# Julia_ABL_Board_V2.net
KiCad netlist of a schematic drawn in EAGLE
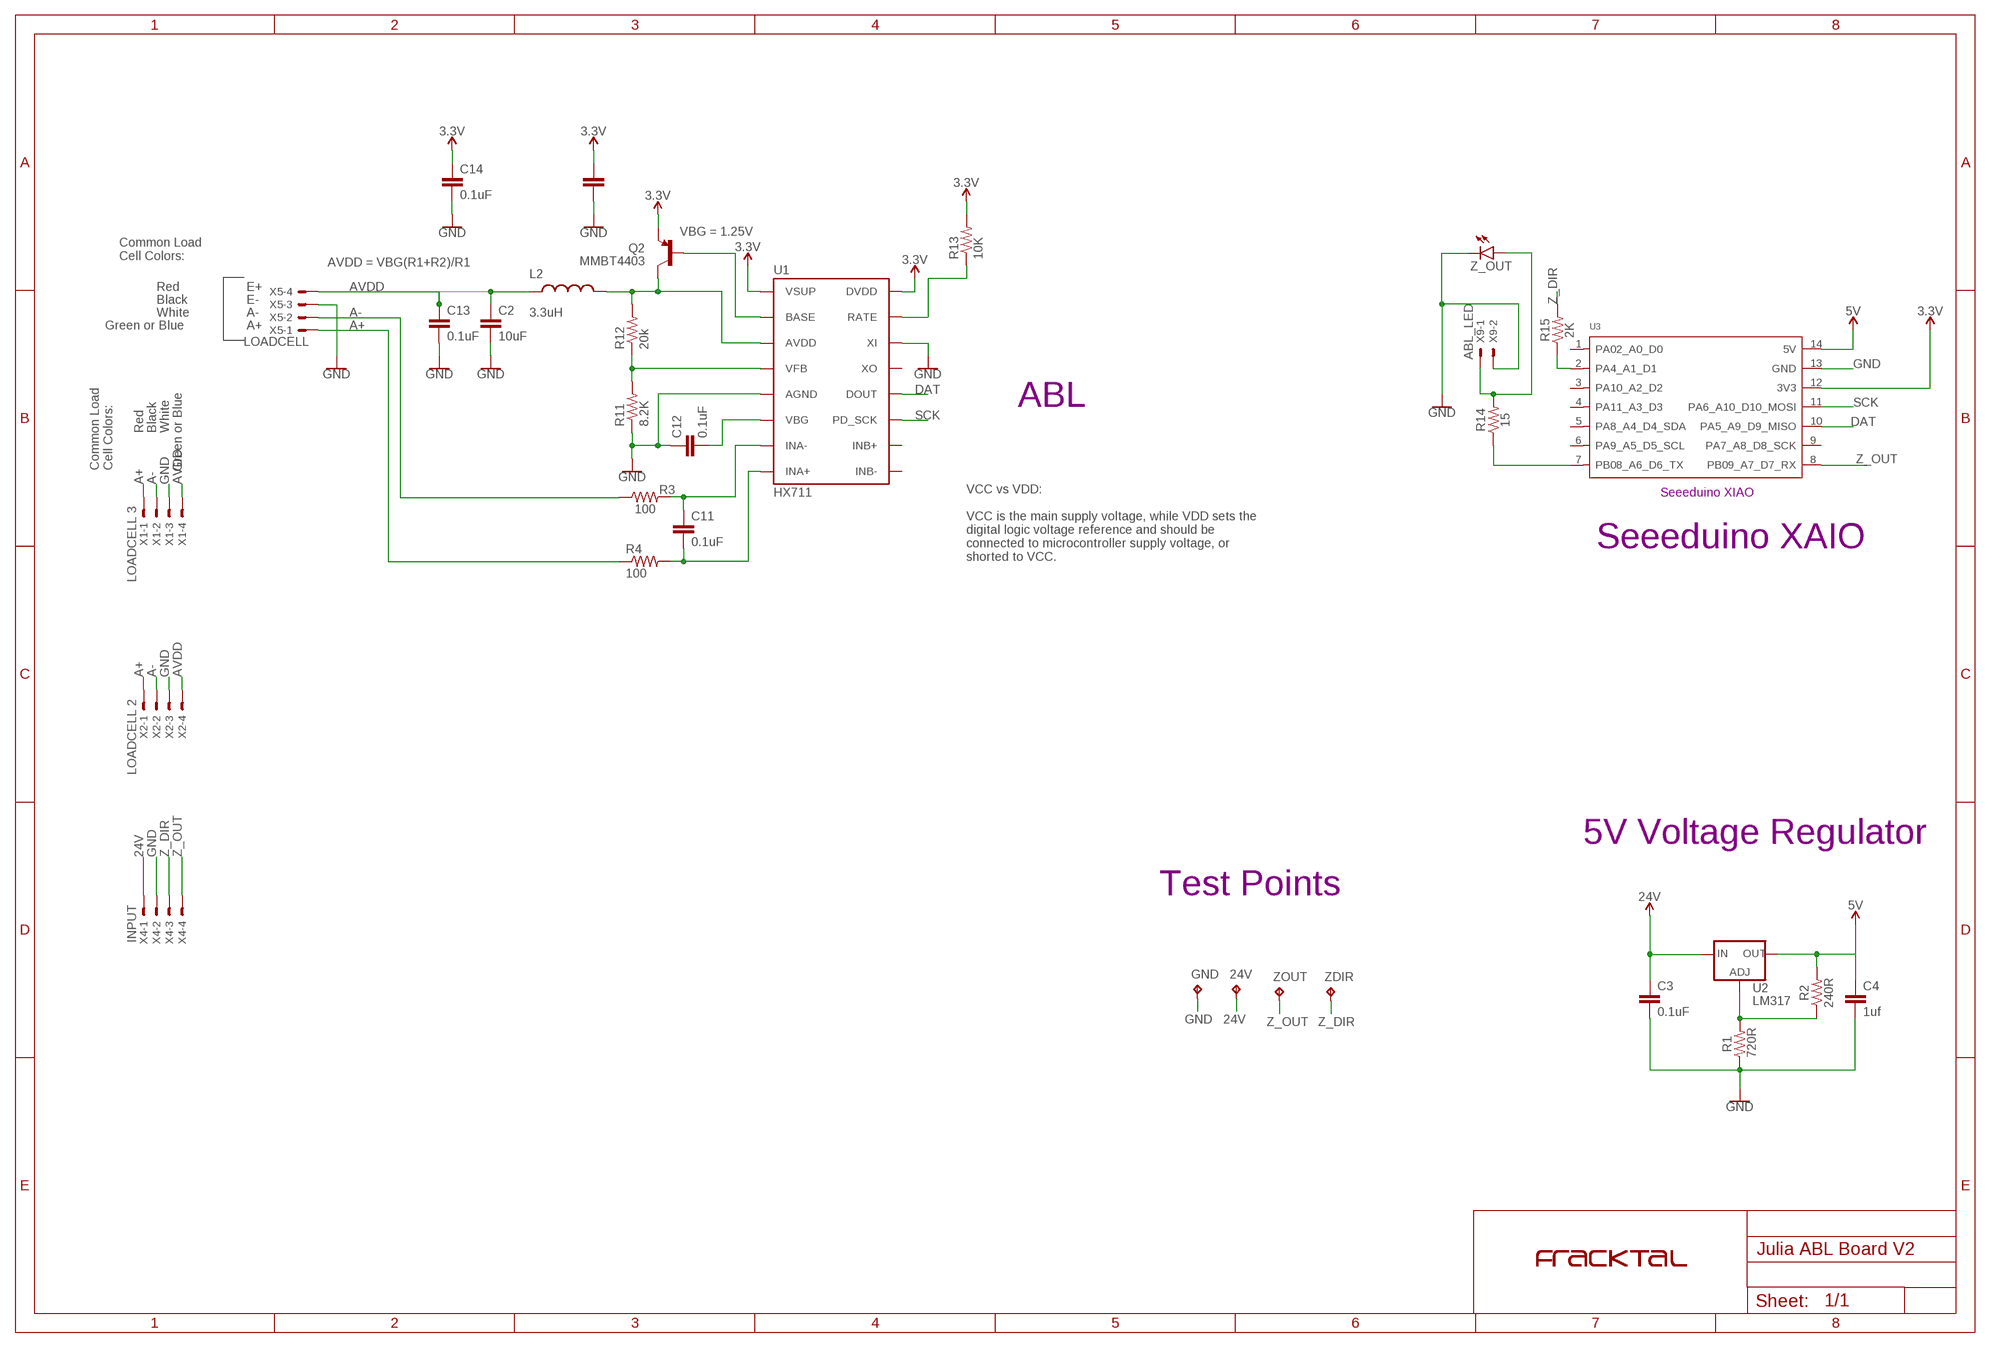
[diagram p0: schematic, sheet 1]

(export (version "E")
  (design (tool "Eeschema 10.0.6"))
  (components
    (comp (ref "24V")
      (value "TPB2,54")
      (footprint "eagle-import:B2,54")
      (libsource (lib "eagle-import") (part "TPB2,54"))
    )
    (comp (ref "C1")
      (value "10uF")
      (footprint "eagle-import:1210")
      (libsource (lib "eagle-import") (part "10UF50V20%(1210)"))
    )
    (comp (ref "C2")
      (value "10uF")
      (footprint "eagle-import:1210")
      (libsource (lib "eagle-import") (part "10UF50V20%(1210)"))
    )
    (comp (ref "C3")
      (value "0.1uF")
      (footprint "eagle-import:0603")
      (libsource (lib "eagle-import") (part "9.0PF-0603-50V-10%"))
    )
    (comp (ref "C4")
      (value "1uf")
      (footprint "eagle-import:0603")
      (libsource (lib "eagle-import") (part "9.0PF-0603-50V-10%"))
    )
    (comp (ref "C11")
      (value "0.1uF")
      (footprint "eagle-import:0603-CAP")
      (libsource (lib "eagle-import") (part "0.1UF-25V-5%(0603)"))
    )
    (comp (ref "C12")
      (value "0.1uF")
      (footprint "eagle-import:0603-CAP")
      (libsource (lib "eagle-import") (part "0.1UF-25V-5%(0603)"))
    )
    (comp (ref "C13")
      (value "0.1uF")
      (footprint "eagle-import:0603-CAP")
      (libsource (lib "eagle-import") (part "0.1UF-25V-5%(0603)"))
    )
    (comp (ref "C14")
      (value "0.1uF")
      (footprint "eagle-import:0603-CAP")
      (libsource (lib "eagle-import") (part "0.1UF-25V-5%(0603)"))
    )
    (comp (ref "GND")
      (value "TPB2,54")
      (footprint "eagle-import:B2,54")
      (libsource (lib "eagle-import") (part "TPB2,54"))
    )
    (comp (ref "L2")
      (value "3.3uH")
      (footprint "eagle-import:0805")
      (libsource (lib "eagle-import") (part "INDUCTOR0805-IND"))
    )
    (comp (ref "Q2")
      (value "MMBT4403")
      (footprint "eagle-import:SOT23-3")
      (libsource (lib "eagle-import") (part "TRANSISTOR_PNPMMBT4403"))
    )
    (comp (ref "R1")
      (value "720R")
      (footprint "eagle-import:0603")
      (libsource (lib "eagle-import") (part "RESISTOR0603"))
    )
    (comp (ref "R2")
      (value "240R")
      (footprint "eagle-import:0603")
      (libsource (lib "eagle-import") (part "RESISTOR0603"))
    )
    (comp (ref "R3")
      (value "100")
      (footprint "eagle-import:0603-RES")
      (libsource (lib "eagle-import") (part "100OHM-1/10W-1%(0603)"))
    )
    (comp (ref "R4")
      (value "100")
      (footprint "eagle-import:0603-RES")
      (libsource (lib "eagle-import") (part "100OHM-1/10W-1%(0603)"))
    )
    (comp (ref "R11")
      (value "8.2K")
      (footprint "eagle-import:0603-RES")
      (libsource (lib "eagle-import") (part "8.2KOHM-1/10W-5%(0603)"))
    )
    (comp (ref "R12")
      (value "20k")
      (footprint "eagle-import:0603-RES")
      (libsource (lib "eagle-import") (part "20KOHM1/10W1%(0603)"))
    )
    (comp (ref "R13")
      (value "10K")
      (footprint "eagle-import:0603-RES")
      (libsource (lib "eagle-import") (part "10KOHM-1/10W-1%(0603)0603"))
    )
    (comp (ref "R14")
      (value "15")
      (footprint "eagle-import:0603")
      (libsource (lib "eagle-import") (part "RESISTOR0603"))
    )
    (comp (ref "R15")
      (value "2K")
      (footprint "eagle-import:0603")
      (libsource (lib "eagle-import") (part "RESISTOR0603"))
    )
    (comp (ref "U$2")
      (value "FRACKTALLOGO")
      (footprint "eagle-import:FRACKTALLOGO")
      (libsource (lib "eagle-import") (part "FRACKTALLOGO"))
    )
    (comp (ref "U1")
      (value "HX711")
      (footprint "eagle-import:SO16")
      (libsource (lib "eagle-import") (part "HX711HX711"))
    )
    (comp (ref "U2")
      (value "LM317")
      (footprint "eagle-import:SOT223")
      (libsource (lib "eagle-import") (part "V_REG_317SMD"))
    )
    (comp (ref "U3")
      (value "MOUDLE-SEEEDUINO-XIAO")
      (footprint "eagle-import:MOUDLE14P-2.54-21X17.8MM")
      (libsource (lib "eagle-import") (part "MOUDLE-SEEEDUINO-XIAO"))
    )
    (comp (ref "X1")
      (value "LOADCELL 3")
      (footprint "eagle-import:JST-XH-04-PACKAGE-LONG-PAD")
      (libsource (lib "eagle-import") (part "JST-XH-04-PIN-LONG-PAD"))
    )
    (comp (ref "X2")
      (value "LOADCELL 2")
      (footprint "eagle-import:JST-XH-04-PACKAGE-LONG-PAD")
      (libsource (lib "eagle-import") (part "JST-XH-04-PIN-LONG-PAD"))
    )
    (comp (ref "X4")
      (value "INPUT")
      (footprint "eagle-import:JST-XH-04-PACKAGE-LONG-PAD")
      (libsource (lib "eagle-import") (part "JST-XH-04-PIN-LONG-PAD"))
    )
    (comp (ref "X5")
      (value "LOADCELL")
      (footprint "eagle-import:JST-XH-04-PACKAGE-LONG-PAD")
      (libsource (lib "eagle-import") (part "JST-XH-04-PIN-LONG-PAD"))
    )
    (comp (ref "X9")
      (value "ABL_LED")
      (footprint "eagle-import:JST-XH-02-PACKAGE-LONG-PAD")
      (libsource (lib "eagle-import") (part "JST-XH-02-PIN-LONG-PAD"))
    )
    (comp (ref "ZDIR")
      (value "TPB2,54")
      (footprint "eagle-import:B2,54")
      (libsource (lib "eagle-import") (part "TPB2,54"))
    )
    (comp (ref "ZOUT")
      (value "TPB2,54")
      (footprint "eagle-import:B2,54")
      (libsource (lib "eagle-import") (part "TPB2,54"))
    )
    (comp (ref "Z_OUT")
      (value "LEDSML0603")
      (footprint "eagle-import:SML0603")
      (libsource (lib "eagle-import") (part "LEDSML0603"))
    )
  )
  (nets
    (net (code "1") (name "/A+") (class "Default")
      (node (ref "R4") (pin "1") (pinfunction "1_1") (pintype "passive"))
      (node (ref "X1") (pin "1") (pinfunction "S_1") (pintype "passive"))
      (node (ref "X2") (pin "1") (pinfunction "S_1") (pintype "passive"))
      (node (ref "X5") (pin "1") (pinfunction "S_1") (pintype "passive"))
    )
    (net (code "2") (name "/A-") (class "Default")
      (node (ref "R3") (pin "1") (pinfunction "1_1") (pintype "passive"))
      (node (ref "X1") (pin "2") (pinfunction "S_2") (pintype "passive"))
      (node (ref "X2") (pin "2") (pinfunction "S_2") (pintype "passive"))
      (node (ref "X5") (pin "2") (pinfunction "S_2") (pintype "passive"))
    )
    (net (code "3") (name "/AVDD") (class "Default")
      (node (ref "C13") (pin "1") (pinfunction "1_1") (pintype "passive"))
      (node (ref "C2") (pin "1") (pinfunction "1_1") (pintype "passive"))
      (node (ref "L2") (pin "1") (pinfunction "1_1") (pintype "passive"))
      (node (ref "X1") (pin "4") (pinfunction "S_4") (pintype "passive"))
      (node (ref "X2") (pin "4") (pinfunction "S_4") (pintype "passive"))
      (node (ref "X5") (pin "4") (pinfunction "S_4") (pintype "passive"))
    )
    (net (code "4") (name "/DAT") (class "Default")
      (node (ref "U1") (pin "12") (pinfunction "DOUT_12") (pintype "bidirectional"))
      (node (ref "U3") (pin "10") (pinfunction "PA5_A9_D9_MISO_10") (pintype "bidirectional"))
    )
    (net (code "5") (name "/SCK") (class "Default")
      (node (ref "U1") (pin "11") (pinfunction "PD_SCK_11") (pintype "bidirectional"))
      (node (ref "U3") (pin "11") (pinfunction "PA6_A10_D10_MOSI_11") (pintype "bidirectional"))
    )
    (net (code "6") (name "/Z_DIR") (class "Default")
      (node (ref "R15") (pin "2") (pinfunction "2_2") (pintype "passive"))
      (node (ref "X4") (pin "3") (pinfunction "S_3") (pintype "passive"))
      (node (ref "ZDIR") (pin "TP") (pinfunction "TP_TP") (pintype "input"))
    )
    (net (code "7") (name "/Z_OUT") (class "Default")
      (node (ref "U3") (pin "8") (pinfunction "PB09_A7_D7_RX_8") (pintype "bidirectional"))
      (node (ref "X4") (pin "4") (pinfunction "S_4") (pintype "passive"))
      (node (ref "ZOUT") (pin "TP") (pinfunction "TP_TP") (pintype "input"))
    )
    (net (code "8") (name "3.3V") (class "Default")
      (node (ref "C1") (pin "1") (pinfunction "1_1") (pintype "passive"))
      (node (ref "C14") (pin "1") (pinfunction "1_1") (pintype "passive"))
      (node (ref "Q2") (pin "2") (pinfunction "E_2") (pintype "passive"))
      (node (ref "R13") (pin "2") (pinfunction "2_2") (pintype "passive"))
      (node (ref "U1") (pin "1") (pinfunction "VSUP_1") (pintype "bidirectional"))
      (node (ref "U1") (pin "16") (pinfunction "DVDD_16") (pintype "bidirectional"))
      (node (ref "U3") (pin "12") (pinfunction "3V3_12") (pintype "bidirectional"))
    )
    (net (code "9") (name "5V") (class "Default")
      (node (ref "C4") (pin "1") (pinfunction "1_1") (pintype "passive"))
      (node (ref "R2") (pin "2") (pinfunction "2_2") (pintype "passive"))
      (node (ref "U2") (pin "2") (pinfunction "OUT_2") (pintype "output"))
      (node (ref "U3") (pin "14") (pinfunction "5V_14") (pintype "bidirectional"))
    )
    (net (code "10") (name "24V") (class "Default")
      (node (ref "24V") (pin "TP") (pinfunction "TP_TP") (pintype "input"))
      (node (ref "C3") (pin "1") (pinfunction "1_1") (pintype "passive"))
      (node (ref "U2") (pin "3") (pinfunction "IN_3") (pintype "input"))
      (node (ref "X4") (pin "1") (pinfunction "S_1") (pintype "passive"))
    )
    (net (code "11") (name "GND") (class "Default")
      (node (ref "C1") (pin "2") (pinfunction "2_2") (pintype "passive"))
      (node (ref "C12") (pin "1") (pinfunction "1_1") (pintype "passive"))
      (node (ref "C13") (pin "2") (pinfunction "2_2") (pintype "passive"))
      (node (ref "C14") (pin "2") (pinfunction "2_2") (pintype "passive"))
      (node (ref "C2") (pin "2") (pinfunction "2_2") (pintype "passive"))
      (node (ref "C3") (pin "2") (pinfunction "2_2") (pintype "passive"))
      (node (ref "C4") (pin "2") (pinfunction "2_2") (pintype "passive"))
      (node (ref "GND") (pin "TP") (pinfunction "TP_TP") (pintype "input"))
      (node (ref "R1") (pin "1") (pinfunction "1_1") (pintype "passive"))
      (node (ref "R11") (pin "1") (pinfunction "1_1") (pintype "passive"))
      (node (ref "U1") (pin "14") (pinfunction "XI_14") (pintype "bidirectional"))
      (node (ref "U1") (pin "5") (pinfunction "AGND_5") (pintype "bidirectional"))
      (node (ref "U3") (pin "13") (pinfunction "GND_13") (pintype "bidirectional"))
      (node (ref "X1") (pin "3") (pinfunction "S_3") (pintype "passive"))
      (node (ref "X2") (pin "3") (pinfunction "S_3") (pintype "passive"))
      (node (ref "X4") (pin "2") (pinfunction "S_2") (pintype "passive"))
      (node (ref "X5") (pin "3") (pinfunction "S_3") (pintype "passive"))
      (node (ref "X9") (pin "2") (pinfunction "S_2") (pintype "passive"))
      (node (ref "Z_OUT") (pin "C") (pinfunction "C_C") (pintype "passive"))
    )
    (net (code "12") (name "Net-(Q2-B)") (class "Default")
      (node (ref "Q2") (pin "1") (pinfunction "B_1") (pintype "passive"))
      (node (ref "U1") (pin "2") (pinfunction "BASE_2") (pintype "bidirectional"))
    )
    (net (code "13") (name "Net-(Q2-C)") (class "Default")
      (node (ref "L2") (pin "2") (pinfunction "2_2") (pintype "passive"))
      (node (ref "Q2") (pin "3") (pinfunction "C_3") (pintype "passive"))
      (node (ref "R12") (pin "2") (pinfunction "2_2") (pintype "passive"))
      (node (ref "U1") (pin "3") (pinfunction "AVDD_3") (pintype "bidirectional"))
    )
    (net (code "14") (name "Net-(U1-INA+)") (class "Default")
      (node (ref "C11") (pin "2") (pinfunction "2_2") (pintype "passive"))
      (node (ref "R4") (pin "2") (pinfunction "2_2") (pintype "passive"))
      (node (ref "U1") (pin "8") (pinfunction "INA+_8") (pintype "bidirectional"))
    )
    (net (code "15") (name "Net-(U1-INA-)") (class "Default")
      (node (ref "C11") (pin "1") (pinfunction "1_1") (pintype "passive"))
      (node (ref "R3") (pin "2") (pinfunction "2_2") (pintype "passive"))
      (node (ref "U1") (pin "7") (pinfunction "INA-_7") (pintype "bidirectional"))
    )
    (net (code "16") (name "Net-(U1-RATE)") (class "Default")
      (node (ref "R13") (pin "1") (pinfunction "1_1") (pintype "passive"))
      (node (ref "U1") (pin "15") (pinfunction "RATE_15") (pintype "bidirectional"))
    )
    (net (code "17") (name "Net-(U1-VBG)") (class "Default")
      (node (ref "C12") (pin "2") (pinfunction "2_2") (pintype "passive"))
      (node (ref "U1") (pin "6") (pinfunction "VBG_6") (pintype "bidirectional"))
    )
    (net (code "18") (name "Net-(U1-VFB)") (class "Default")
      (node (ref "R11") (pin "2") (pinfunction "2_2") (pintype "passive"))
      (node (ref "R12") (pin "1") (pinfunction "1_1") (pintype "passive"))
      (node (ref "U1") (pin "4") (pinfunction "VFB_4") (pintype "bidirectional"))
    )
    (net (code "19") (name "Net-(U2-ADJ)") (class "Default")
      (node (ref "R1") (pin "2") (pinfunction "2_2") (pintype "passive"))
      (node (ref "R2") (pin "1") (pinfunction "1_1") (pintype "passive"))
      (node (ref "U2") (pin "1") (pinfunction "ADJ_1") (pintype "input"))
    )
    (net (code "20") (name "Net-(U3-PA4_A1_D1)") (class "Default")
      (node (ref "R15") (pin "1") (pinfunction "1_1") (pintype "passive"))
      (node (ref "U3") (pin "2") (pinfunction "PA4_A1_D1_2") (pintype "bidirectional"))
    )
    (net (code "21") (name "Net-(U3-PB08_A6_D6_TX)") (class "Default")
      (node (ref "R14") (pin "1") (pinfunction "1_1") (pintype "passive"))
      (node (ref "U3") (pin "7") (pinfunction "PB08_A6_D6_TX_7") (pintype "bidirectional"))
    )
    (net (code "22") (name "Net-(X9A-S)") (class "Default")
      (node (ref "R14") (pin "2") (pinfunction "2_2") (pintype "passive"))
      (node (ref "X9") (pin "1") (pinfunction "S_1") (pintype "passive"))
      (node (ref "Z_OUT") (pin "A") (pinfunction "A_A") (pintype "passive"))
    )
    (net (code "23") (name "unconnected-(U1-INB+-Pad10)") (class "Default")
      (node (ref "U1") (pin "10") (pinfunction "INB+_10") (pintype "bidirectional"))
    )
    (net (code "24") (name "unconnected-(U1-INB--Pad9)") (class "Default")
      (node (ref "U1") (pin "9") (pinfunction "INB-_9") (pintype "bidirectional"))
    )
    (net (code "25") (name "unconnected-(U1-XO-Pad13)") (class "Default")
      (node (ref "U1") (pin "13") (pinfunction "XO_13") (pintype "bidirectional"))
    )
    (net (code "26") (name "unconnected-(U3-PA02_A0_D0-Pad1)") (class "Default")
      (node (ref "U3") (pin "1") (pinfunction "PA02_A0_D0_1") (pintype "bidirectional"))
    )
    (net (code "27") (name "unconnected-(U3-PA7_A8_D8_SCK-Pad9)") (class "Default")
      (node (ref "U3") (pin "9") (pinfunction "PA7_A8_D8_SCK_9") (pintype "bidirectional"))
    )
    (net (code "28") (name "unconnected-(U3-PA8_A4_D4_SDA-Pad5)") (class "Default")
      (node (ref "U3") (pin "5") (pinfunction "PA8_A4_D4_SDA_5") (pintype "bidirectional"))
    )
    (net (code "29") (name "unconnected-(U3-PA9_A5_D5_SCL-Pad6)") (class "Default")
      (node (ref "U3") (pin "6") (pinfunction "PA9_A5_D5_SCL_6") (pintype "bidirectional"))
    )
    (net (code "30") (name "unconnected-(U3-PA10_A2_D2-Pad3)") (class "Default")
      (node (ref "U3") (pin "3") (pinfunction "PA10_A2_D2_3") (pintype "bidirectional"))
    )
    (net (code "31") (name "unconnected-(U3-PA11_A3_D3-Pad4)") (class "Default")
      (node (ref "U3") (pin "4") (pinfunction "PA11_A3_D3_4") (pintype "bidirectional"))
    )
  )
)
